# SendSlice.net
KiCad netlist of a schematic drawn in EAGLE
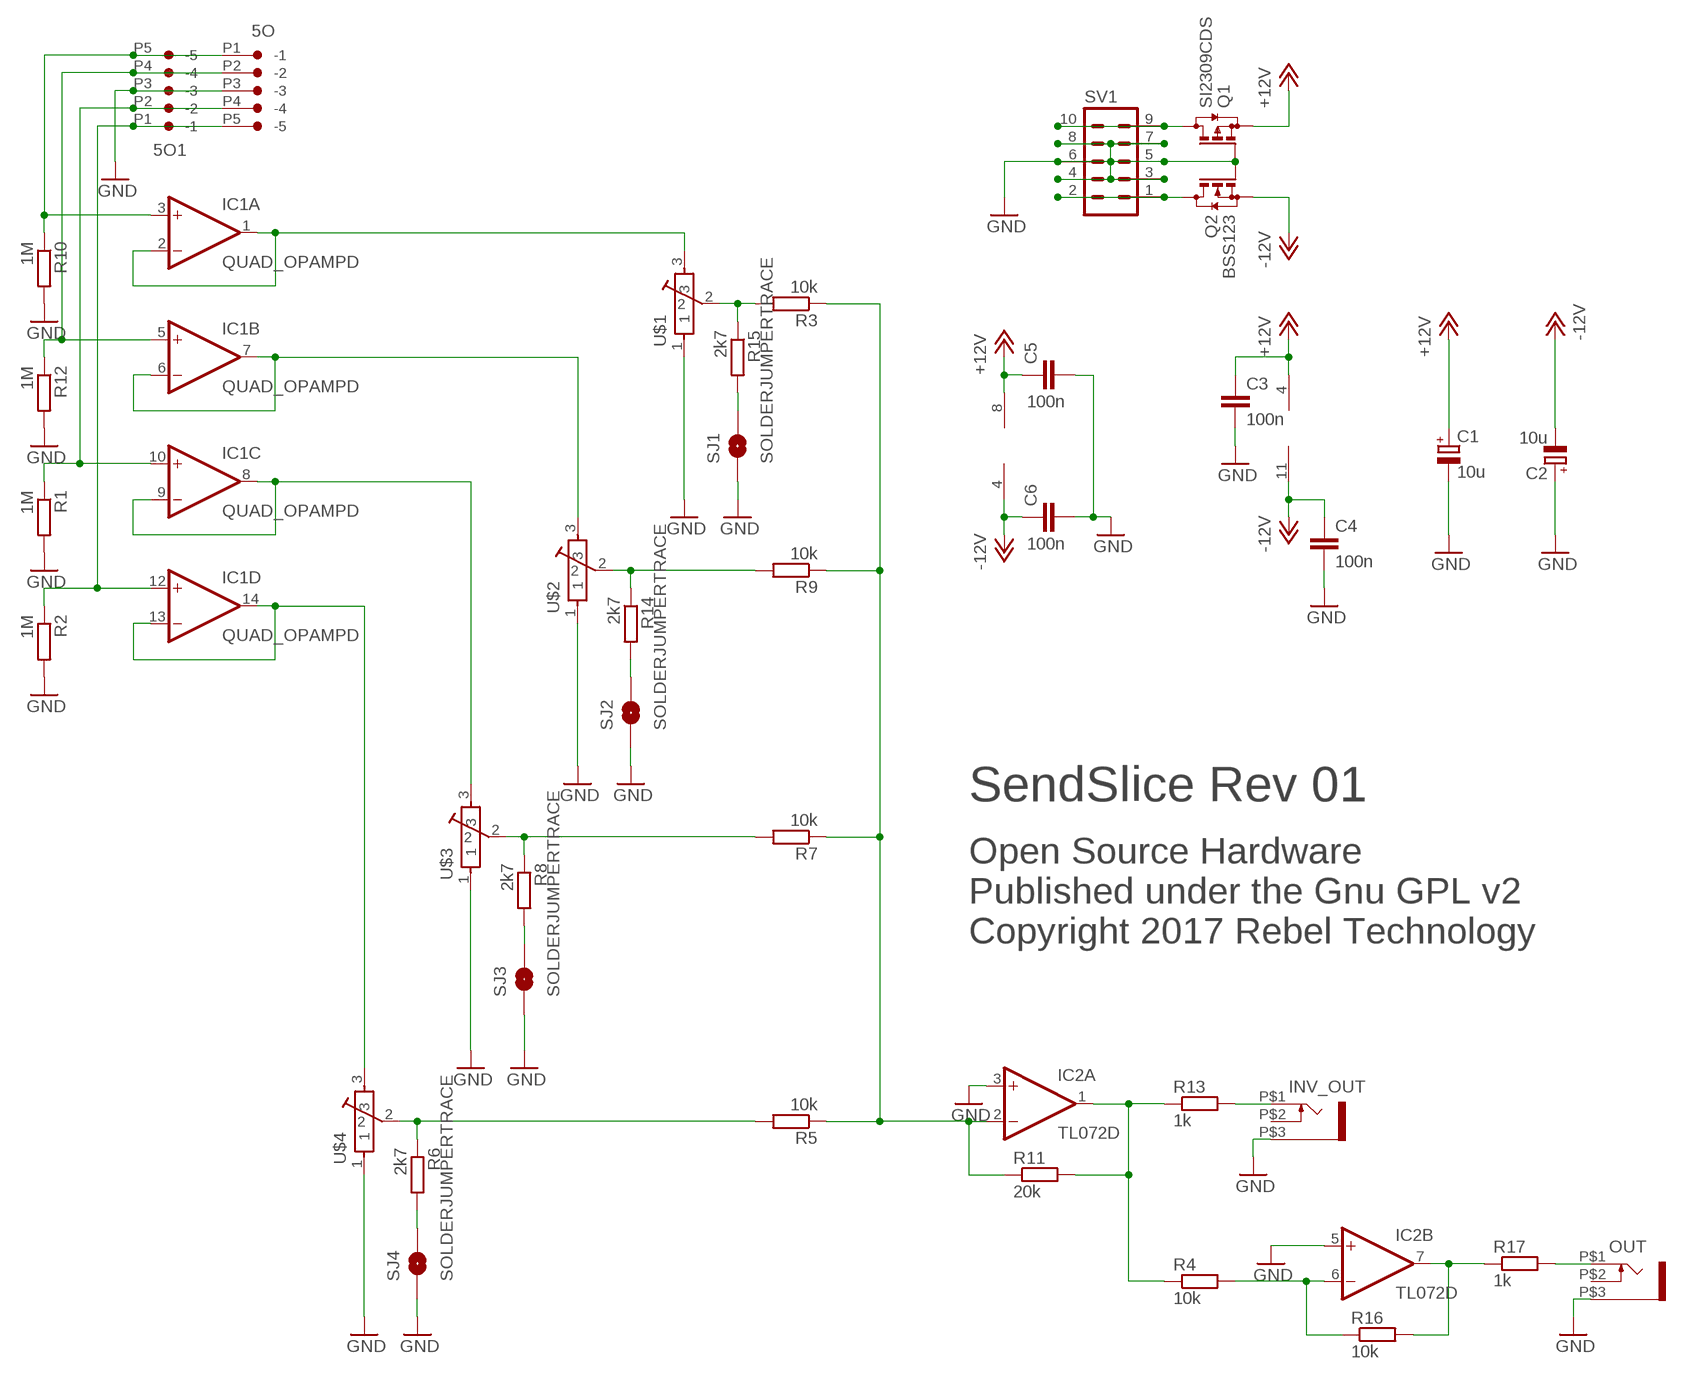
[diagram p0: schematic, sheet 1]

(export (version "E")
  (design (tool "Eeschema 10.0.6"))
  (components
    (comp (ref "5O")
      (value "CON-JST_PH_5W")
      (footprint "eagle-import:CON-JST_PH_5W")
      (libsource (lib "eagle-import") (part "CON-JST_PH_5W"))
    )
    (comp (ref "5O1")
      (value "CON-JST_PH_5W")
      (footprint "eagle-import:CON-JST_PH_5W")
      (libsource (lib "eagle-import") (part "CON-JST_PH_5W"))
    )
    (comp (ref "C1")
      (value "10u")
      (footprint "eagle-import:153CLV-0505")
      (libsource (lib "eagle-import") (part "CPOL-EU153CLV-0505"))
    )
    (comp (ref "C2")
      (value "10u")
      (footprint "eagle-import:153CLV-0505")
      (libsource (lib "eagle-import") (part "CPOL-EU153CLV-0505"))
    )
    (comp (ref "C3")
      (value "100n")
      (footprint "eagle-import:C0603")
      (libsource (lib "eagle-import") (part "C-EUC0603"))
    )
    (comp (ref "C4")
      (value "100n")
      (footprint "eagle-import:C0603")
      (libsource (lib "eagle-import") (part "C-EUC0603"))
    )
    (comp (ref "C5")
      (value "100n")
      (footprint "eagle-import:C0603")
      (libsource (lib "eagle-import") (part "C-EUC0603"))
    )
    (comp (ref "C6")
      (value "100n")
      (footprint "eagle-import:C0603")
      (libsource (lib "eagle-import") (part "C-EUC0603"))
    )
    (comp (ref "IC1")
      (value "QUAD_OPAMPD")
      (footprint "eagle-import:SO14")
      (libsource (lib "eagle-import") (part "QUAD_OPAMPD"))
    )
    (comp (ref "IC2")
      (value "TL072D")
      (footprint "eagle-import:SO08")
      (libsource (lib "eagle-import") (part "TL072D"))
    )
    (comp (ref "INV_OUT")
      (value "JACK-UJ-3502-R")
      (footprint "eagle-import:UJ-3502-R")
      (libsource (lib "eagle-import") (part "JACK-UJ-3502-R"))
    )
    (comp (ref "OUT")
      (value "JACK-UJ-3502-R")
      (footprint "eagle-import:UJ-3502-R")
      (libsource (lib "eagle-import") (part "JACK-UJ-3502-R"))
    )
    (comp (ref "Q1")
      (value "SI2309CDS")
      (footprint "eagle-import:SOT23")
      (libsource (lib "eagle-import") (part "BSS84"))
    )
    (comp (ref "Q2")
      (value "BSS123")
      (footprint "eagle-import:SOT23")
      (libsource (lib "eagle-import") (part "BSS123"))
    )
    (comp (ref "R1")
      (value "1M")
      (footprint "eagle-import:0603")
      (libsource (lib "eagle-import") (part "R-EU_0603"))
    )
    (comp (ref "R2")
      (value "1M")
      (footprint "eagle-import:0603")
      (libsource (lib "eagle-import") (part "R-EU_0603"))
    )
    (comp (ref "R3")
      (value "10k")
      (footprint "eagle-import:0603")
      (libsource (lib "eagle-import") (part "R-EU_0603"))
    )
    (comp (ref "R4")
      (value "10k")
      (footprint "eagle-import:0603")
      (libsource (lib "eagle-import") (part "R-EU_0603"))
    )
    (comp (ref "R5")
      (value "10k")
      (footprint "eagle-import:0603")
      (libsource (lib "eagle-import") (part "R-EU_0603"))
    )
    (comp (ref "R6")
      (value "2k7")
      (footprint "eagle-import:0603")
      (libsource (lib "eagle-import") (part "R-EU_0603"))
    )
    (comp (ref "R7")
      (value "10k")
      (footprint "eagle-import:0603")
      (libsource (lib "eagle-import") (part "R-EU_0603"))
    )
    (comp (ref "R8")
      (value "2k7")
      (footprint "eagle-import:0603")
      (libsource (lib "eagle-import") (part "R-EU_0603"))
    )
    (comp (ref "R9")
      (value "10k")
      (footprint "eagle-import:0603")
      (libsource (lib "eagle-import") (part "R-EU_0603"))
    )
    (comp (ref "R10")
      (value "1M")
      (footprint "eagle-import:0603")
      (libsource (lib "eagle-import") (part "R-EU_0603"))
    )
    (comp (ref "R11")
      (value "20k")
      (footprint "eagle-import:0603")
      (libsource (lib "eagle-import") (part "R-EU_0603"))
    )
    (comp (ref "R12")
      (value "1M")
      (footprint "eagle-import:0603")
      (libsource (lib "eagle-import") (part "R-EU_0603"))
    )
    (comp (ref "R13")
      (value "1k")
      (footprint "eagle-import:0603")
      (libsource (lib "eagle-import") (part "R-EU_0603"))
    )
    (comp (ref "R14")
      (value "2k7")
      (footprint "eagle-import:0603")
      (libsource (lib "eagle-import") (part "R-EU_0603"))
    )
    (comp (ref "R15")
      (value "2k7")
      (footprint "eagle-import:0603")
      (libsource (lib "eagle-import") (part "R-EU_0603"))
    )
    (comp (ref "R16")
      (value "10k")
      (footprint "eagle-import:0603")
      (libsource (lib "eagle-import") (part "R-EU_0603"))
    )
    (comp (ref "R17")
      (value "1k")
      (footprint "eagle-import:0603")
      (libsource (lib "eagle-import") (part "R-EU_0603"))
    )
    (comp (ref "SJ1")
      (value "SOLDERJUMPERTRACE")
      (footprint "eagle-import:SJ_2S-TRACE")
      (libsource (lib "eagle-import") (part "SOLDERJUMPERTRACE"))
    )
    (comp (ref "SJ2")
      (value "SOLDERJUMPERTRACE")
      (footprint "eagle-import:SJ_2S-TRACE")
      (libsource (lib "eagle-import") (part "SOLDERJUMPERTRACE"))
    )
    (comp (ref "SJ3")
      (value "SOLDERJUMPERTRACE")
      (footprint "eagle-import:SJ_2S-TRACE")
      (libsource (lib "eagle-import") (part "SOLDERJUMPERTRACE"))
    )
    (comp (ref "SJ4")
      (value "SOLDERJUMPERTRACE")
      (footprint "eagle-import:SJ_2S-TRACE")
      (libsource (lib "eagle-import") (part "SOLDERJUMPERTRACE"))
    )
    (comp (ref "SV1")
      (value "MA05-2")
      (footprint "eagle-import:MA05-2")
      (libsource (lib "eagle-import") (part "MA05-2"))
    )
    (comp (ref "U$1")
      (value "10k lin")
      (footprint "eagle-import:POT-BOURNS-PTD901")
      (libsource (lib "eagle-import") (part "POT-BOURNS-PTD901"))
    )
    (comp (ref "U$2")
      (value "10k lin")
      (footprint "eagle-import:POT-BOURNS-PTD901")
      (libsource (lib "eagle-import") (part "POT-BOURNS-PTD901"))
    )
    (comp (ref "U$3")
      (value "10k lin")
      (footprint "eagle-import:POT-BOURNS-PTD901")
      (libsource (lib "eagle-import") (part "POT-BOURNS-PTD901"))
    )
    (comp (ref "U$4")
      (value "10k lin")
      (footprint "eagle-import:POT-BOURNS-PTD901")
      (libsource (lib "eagle-import") (part "POT-BOURNS-PTD901"))
    )
  )
  (nets
    (net (code "1") (name "+12V") (class "Default")
      (node (ref "C1") (pin "+") (pinfunction "+_+") (pintype "passive"))
      (node (ref "C3") (pin "1") (pinfunction "1_1") (pintype "passive"))
      (node (ref "C5") (pin "1") (pinfunction "1_1") (pintype "passive"))
      (node (ref "IC1") (pin "4") (pinfunction "V+_4") (pintype "power_in"))
      (node (ref "IC2") (pin "8") (pinfunction "V+_8") (pintype "power_in"))
      (node (ref "Q1") (pin "2") (pinfunction "S_2") (pintype "passive"))
    )
    (net (code "2") (name "-12V") (class "Default")
      (node (ref "C2") (pin "-") (pinfunction "-_-") (pintype "passive"))
      (node (ref "C4") (pin "1") (pinfunction "1_1") (pintype "passive"))
      (node (ref "C6") (pin "1") (pinfunction "1_1") (pintype "passive"))
      (node (ref "IC1") (pin "11") (pinfunction "V-_11") (pintype "power_in"))
      (node (ref "IC2") (pin "4") (pinfunction "V-_4") (pintype "power_in"))
      (node (ref "Q2") (pin "2") (pinfunction "S_2") (pintype "passive"))
    )
    (net (code "3") (name "GND") (class "Default")
      (node (ref "5O") (pin "P3") (pinfunction "-3_P3") (pintype "bidirectional"))
      (node (ref "5O1") (pin "P3") (pinfunction "-3_P3") (pintype "bidirectional"))
      (node (ref "C1") (pin "-") (pinfunction "-_-") (pintype "passive"))
      (node (ref "C2") (pin "+") (pinfunction "+_+") (pintype "passive"))
      (node (ref "C3") (pin "2") (pinfunction "2_2") (pintype "passive"))
      (node (ref "C4") (pin "2") (pinfunction "2_2") (pintype "passive"))
      (node (ref "C5") (pin "2") (pinfunction "2_2") (pintype "passive"))
      (node (ref "C6") (pin "2") (pinfunction "2_2") (pintype "passive"))
      (node (ref "IC2") (pin "3") (pinfunction "+IN_3") (pintype "input"))
      (node (ref "IC2") (pin "5") (pinfunction "+IN_5") (pintype "input"))
      (node (ref "INV_OUT") (pin "P$3") (pinfunction "SLEEVE_P$3") (pintype "passive"))
      (node (ref "OUT") (pin "P$3") (pinfunction "SLEEVE_P$3") (pintype "passive"))
      (node (ref "Q1") (pin "1") (pinfunction "G_1") (pintype "passive"))
      (node (ref "Q2") (pin "1") (pinfunction "G_1") (pintype "passive"))
      (node (ref "R1") (pin "2") (pinfunction "2_2") (pintype "passive"))
      (node (ref "R10") (pin "2") (pinfunction "2_2") (pintype "passive"))
      (node (ref "R12") (pin "2") (pinfunction "2_2") (pintype "passive"))
      (node (ref "R2") (pin "2") (pinfunction "2_2") (pintype "passive"))
      (node (ref "SJ1") (pin "1") (pinfunction "1_1") (pintype "passive"))
      (node (ref "SJ2") (pin "1") (pinfunction "1_1") (pintype "passive"))
      (node (ref "SJ3") (pin "1") (pinfunction "1_1") (pintype "passive"))
      (node (ref "SJ4") (pin "1") (pinfunction "1_1") (pintype "passive"))
      (node (ref "SV1") (pin "3") (pinfunction "3_3") (pintype "passive"))
      (node (ref "SV1") (pin "4") (pinfunction "4_4") (pintype "passive"))
      (node (ref "SV1") (pin "5") (pinfunction "5_5") (pintype "passive"))
      (node (ref "SV1") (pin "6") (pinfunction "6_6") (pintype "passive"))
      (node (ref "SV1") (pin "7") (pinfunction "7_7") (pintype "passive"))
      (node (ref "SV1") (pin "8") (pinfunction "8_8") (pintype "passive"))
      (node (ref "U$1") (pin "1") (pinfunction "1_1") (pintype "bidirectional"))
      (node (ref "U$2") (pin "1") (pinfunction "1_1") (pintype "bidirectional"))
      (node (ref "U$3") (pin "1") (pinfunction "1_1") (pintype "bidirectional"))
      (node (ref "U$4") (pin "1") (pinfunction "1_1") (pintype "bidirectional"))
    )
    (net (code "4") (name "Net-(5O--1)") (class "Default")
      (node (ref "5O") (pin "P1") (pinfunction "-1_P1") (pintype "bidirectional"))
      (node (ref "5O1") (pin "P5") (pinfunction "-5_P5") (pintype "bidirectional"))
      (node (ref "IC1") (pin "3") (pinfunction "+IN_3") (pintype "input"))
      (node (ref "R10") (pin "1") (pinfunction "1_1") (pintype "passive"))
    )
    (net (code "5") (name "Net-(5O--2)") (class "Default")
      (node (ref "5O") (pin "P2") (pinfunction "-2_P2") (pintype "bidirectional"))
      (node (ref "5O1") (pin "P4") (pinfunction "-4_P4") (pintype "bidirectional"))
      (node (ref "IC1") (pin "5") (pinfunction "+IN_5") (pintype "input"))
      (node (ref "R12") (pin "1") (pinfunction "1_1") (pintype "passive"))
    )
    (net (code "6") (name "Net-(5O--4)") (class "Default")
      (node (ref "5O") (pin "P4") (pinfunction "-4_P4") (pintype "bidirectional"))
      (node (ref "5O1") (pin "P2") (pinfunction "-2_P2") (pintype "bidirectional"))
      (node (ref "IC1") (pin "10") (pinfunction "+IN_10") (pintype "input"))
      (node (ref "R1") (pin "1") (pinfunction "1_1") (pintype "passive"))
    )
    (net (code "7") (name "Net-(5O--5)") (class "Default")
      (node (ref "5O") (pin "P5") (pinfunction "-5_P5") (pintype "bidirectional"))
      (node (ref "5O1") (pin "P1") (pinfunction "-1_P1") (pintype "bidirectional"))
      (node (ref "IC1") (pin "12") (pinfunction "+IN_12") (pintype "input"))
      (node (ref "R2") (pin "1") (pinfunction "1_1") (pintype "passive"))
    )
    (net (code "8") (name "Net-(IC1A--IN)") (class "Default")
      (node (ref "IC1") (pin "1") (pinfunction "OUT_1") (pintype "output"))
      (node (ref "IC1") (pin "2") (pinfunction "-IN_2") (pintype "input"))
      (node (ref "U$1") (pin "3") (pinfunction "3_3") (pintype "bidirectional"))
    )
    (net (code "9") (name "Net-(IC1B--IN)") (class "Default")
      (node (ref "IC1") (pin "6") (pinfunction "-IN_6") (pintype "input"))
      (node (ref "IC1") (pin "7") (pinfunction "OUT_7") (pintype "output"))
      (node (ref "U$2") (pin "3") (pinfunction "3_3") (pintype "bidirectional"))
    )
    (net (code "10") (name "Net-(IC1C--IN)") (class "Default")
      (node (ref "IC1") (pin "8") (pinfunction "OUT_8") (pintype "output"))
      (node (ref "IC1") (pin "9") (pinfunction "-IN_9") (pintype "input"))
      (node (ref "U$3") (pin "3") (pinfunction "3_3") (pintype "bidirectional"))
    )
    (net (code "11") (name "Net-(IC1D--IN)") (class "Default")
      (node (ref "IC1") (pin "13") (pinfunction "-IN_13") (pintype "input"))
      (node (ref "IC1") (pin "14") (pinfunction "OUT_14") (pintype "output"))
      (node (ref "U$4") (pin "3") (pinfunction "3_3") (pintype "bidirectional"))
    )
    (net (code "12") (name "Net-(IC2A--IN)") (class "Default")
      (node (ref "IC2") (pin "2") (pinfunction "-IN_2") (pintype "input"))
      (node (ref "R11") (pin "1") (pinfunction "1_1") (pintype "passive"))
      (node (ref "R3") (pin "1") (pinfunction "1_1") (pintype "passive"))
      (node (ref "R5") (pin "1") (pinfunction "1_1") (pintype "passive"))
      (node (ref "R7") (pin "1") (pinfunction "1_1") (pintype "passive"))
      (node (ref "R9") (pin "1") (pinfunction "1_1") (pintype "passive"))
    )
    (net (code "13") (name "Net-(IC2A-OUT)") (class "Default")
      (node (ref "IC2") (pin "1") (pinfunction "OUT_1") (pintype "output"))
      (node (ref "R11") (pin "2") (pinfunction "2_2") (pintype "passive"))
      (node (ref "R13") (pin "1") (pinfunction "1_1") (pintype "passive"))
      (node (ref "R4") (pin "1") (pinfunction "1_1") (pintype "passive"))
    )
    (net (code "14") (name "Net-(IC2B--IN)") (class "Default")
      (node (ref "IC2") (pin "6") (pinfunction "-IN_6") (pintype "input"))
      (node (ref "R16") (pin "1") (pinfunction "1_1") (pintype "passive"))
      (node (ref "R4") (pin "2") (pinfunction "2_2") (pintype "passive"))
    )
    (net (code "15") (name "Net-(IC2B-OUT)") (class "Default")
      (node (ref "IC2") (pin "7") (pinfunction "OUT_7") (pintype "output"))
      (node (ref "R16") (pin "2") (pinfunction "2_2") (pintype "passive"))
      (node (ref "R17") (pin "1") (pinfunction "1_1") (pintype "passive"))
    )
    (net (code "16") (name "Net-(INV_OUT-TIP)") (class "Default")
      (node (ref "INV_OUT") (pin "P$1") (pinfunction "TIP_P$1") (pintype "passive"))
      (node (ref "R13") (pin "2") (pinfunction "2_2") (pintype "passive"))
    )
    (net (code "17") (name "Net-(OUT-TIP)") (class "Default")
      (node (ref "OUT") (pin "P$1") (pinfunction "TIP_P$1") (pintype "passive"))
      (node (ref "R17") (pin "2") (pinfunction "2_2") (pintype "passive"))
    )
    (net (code "18") (name "Net-(Q1-D)") (class "Default")
      (node (ref "Q1") (pin "3") (pinfunction "D_3") (pintype "passive"))
      (node (ref "SV1") (pin "10") (pinfunction "10_10") (pintype "passive"))
      (node (ref "SV1") (pin "9") (pinfunction "9_9") (pintype "passive"))
    )
    (net (code "19") (name "Net-(Q2-D)") (class "Default")
      (node (ref "Q2") (pin "3") (pinfunction "D_3") (pintype "passive"))
      (node (ref "SV1") (pin "1") (pinfunction "1_1") (pintype "passive"))
      (node (ref "SV1") (pin "2") (pinfunction "2_2") (pintype "passive"))
    )
    (net (code "20") (name "Net-(R5-Pad2)") (class "Default")
      (node (ref "R5") (pin "2") (pinfunction "2_2") (pintype "passive"))
      (node (ref "R6") (pin "1") (pinfunction "1_1") (pintype "passive"))
      (node (ref "U$4") (pin "2") (pinfunction "2_2") (pintype "bidirectional"))
    )
    (net (code "21") (name "Net-(R6-Pad2)") (class "Default")
      (node (ref "R6") (pin "2") (pinfunction "2_2") (pintype "passive"))
      (node (ref "SJ4") (pin "2") (pinfunction "2_2") (pintype "passive"))
    )
    (net (code "22") (name "Net-(R7-Pad2)") (class "Default")
      (node (ref "R7") (pin "2") (pinfunction "2_2") (pintype "passive"))
      (node (ref "R8") (pin "1") (pinfunction "1_1") (pintype "passive"))
      (node (ref "U$3") (pin "2") (pinfunction "2_2") (pintype "bidirectional"))
    )
    (net (code "23") (name "Net-(R8-Pad2)") (class "Default")
      (node (ref "R8") (pin "2") (pinfunction "2_2") (pintype "passive"))
      (node (ref "SJ3") (pin "2") (pinfunction "2_2") (pintype "passive"))
    )
    (net (code "24") (name "Net-(R14-Pad1)") (class "Default")
      (node (ref "R14") (pin "1") (pinfunction "1_1") (pintype "passive"))
      (node (ref "R9") (pin "2") (pinfunction "2_2") (pintype "passive"))
      (node (ref "U$2") (pin "2") (pinfunction "2_2") (pintype "bidirectional"))
    )
    (net (code "25") (name "Net-(R14-Pad2)") (class "Default")
      (node (ref "R14") (pin "2") (pinfunction "2_2") (pintype "passive"))
      (node (ref "SJ2") (pin "2") (pinfunction "2_2") (pintype "passive"))
    )
    (net (code "26") (name "Net-(R15-Pad1)") (class "Default")
      (node (ref "R15") (pin "1") (pinfunction "1_1") (pintype "passive"))
      (node (ref "R3") (pin "2") (pinfunction "2_2") (pintype "passive"))
      (node (ref "U$1") (pin "2") (pinfunction "2_2") (pintype "bidirectional"))
    )
    (net (code "27") (name "Net-(R15-Pad2)") (class "Default")
      (node (ref "R15") (pin "2") (pinfunction "2_2") (pintype "passive"))
      (node (ref "SJ1") (pin "2") (pinfunction "2_2") (pintype "passive"))
    )
    (net (code "28") (name "unconnected-(INV_OUT-SW-PadP$2)") (class "Default")
      (node (ref "INV_OUT") (pin "P$2") (pinfunction "SW_P$2") (pintype "passive"))
    )
    (net (code "29") (name "unconnected-(OUT-SW-PadP$2)") (class "Default")
      (node (ref "OUT") (pin "P$2") (pinfunction "SW_P$2") (pintype "passive"))
    )
  )
)
